# v1-hbridge.net
KiCad netlist of a schematic drawn in EAGLE
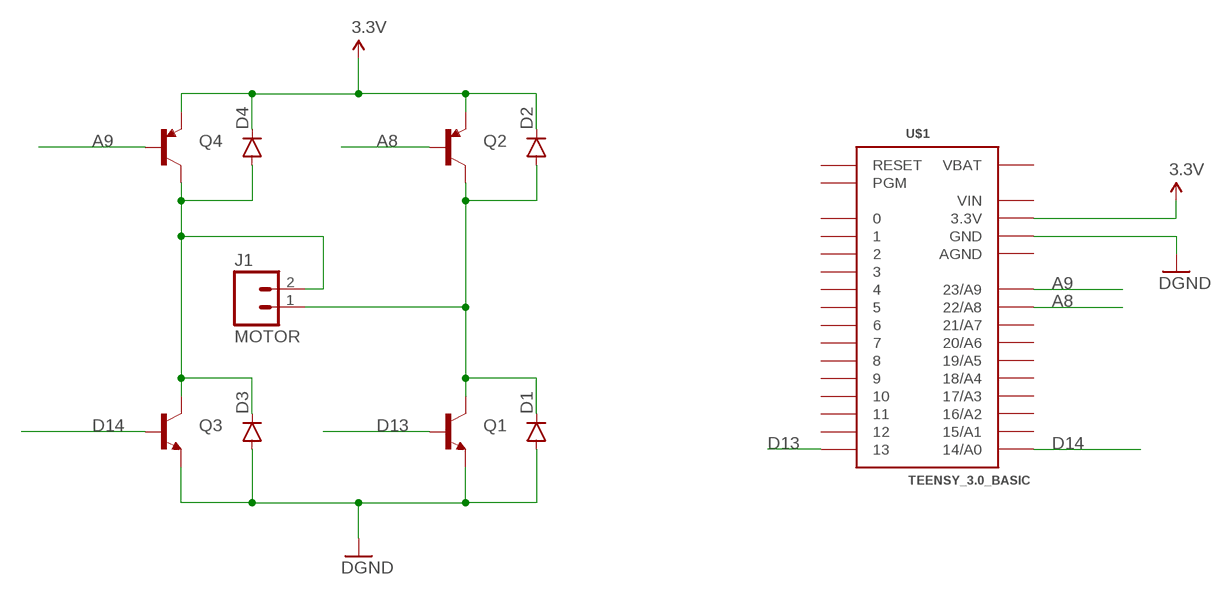
[diagram p0: schematic, sheet 1]

(export (version "E")
  (design (tool "Eeschema 10.0.6"))
  (components
    (comp (ref "D1")
      (value "DIODE")
      (footprint "eagle-import:DIODE-1N4001-KIT")
      (libsource (lib "eagle-import") (part "DIODE"))
    )
    (comp (ref "D2")
      (value "DIODE")
      (footprint "eagle-import:DIODE-1N4001-KIT")
      (libsource (lib "eagle-import") (part "DIODE"))
    )
    (comp (ref "D3")
      (value "DIODE")
      (footprint "eagle-import:DIODE-1N4001-KIT")
      (libsource (lib "eagle-import") (part "DIODE"))
    )
    (comp (ref "D4")
      (value "DIODE")
      (footprint "eagle-import:DIODE-1N4001-KIT")
      (libsource (lib "eagle-import") (part "DIODE"))
    )
    (comp (ref "J1")
      (value "MOTOR")
      (footprint "eagle-import:1X02_LOCK")
      (libsource (lib "eagle-import") (part "M02LOCK"))
    )
    (comp (ref "Q1")
      (value "TRANSISTOR_NPNBC547")
      (footprint "eagle-import:TO-92-AMMO")
      (libsource (lib "eagle-import") (part "TRANSISTOR_NPNBC547"))
    )
    (comp (ref "Q2")
      (value "TRANSISTOR_PNPTO92")
      (footprint "eagle-import:TO-92")
      (libsource (lib "eagle-import") (part "TRANSISTOR_PNPTO92"))
    )
    (comp (ref "Q3")
      (value "TRANSISTOR_NPNBC547")
      (footprint "eagle-import:TO-92-AMMO")
      (libsource (lib "eagle-import") (part "TRANSISTOR_NPNBC547"))
    )
    (comp (ref "Q4")
      (value "TRANSISTOR_PNPTO92")
      (footprint "eagle-import:TO-92")
      (libsource (lib "eagle-import") (part "TRANSISTOR_PNPTO92"))
    )
    (comp (ref "U$1")
      (value "TEENSY_3.0_BASIC")
      (footprint "eagle-import:TEENSY_3.0_BASIC")
      (libsource (lib "eagle-import") (part "TEENSY_3.0_BASIC"))
    )
  )
  (nets
    (net (code "1") (name "/A8") (class "Default")
      (node (ref "Q2") (pin "2") (pinfunction "B_2") (pintype "passive"))
      (node (ref "U$1") (pin "22/A8") (pinfunction "22/A8_22/A8") (pintype "bidirectional"))
    )
    (net (code "2") (name "/A9") (class "Default")
      (node (ref "Q4") (pin "2") (pinfunction "B_2") (pintype "passive"))
      (node (ref "U$1") (pin "23/A9") (pinfunction "23/A9_23/A9") (pintype "bidirectional"))
    )
    (net (code "3") (name "/AGND") (class "Default")
      (node (ref "U$1") (pin "AGND") (pinfunction "AGND_AGND") (pintype "power_in"))
    )
    (net (code "4") (name "/D13") (class "Default")
      (node (ref "Q1") (pin "2") (pinfunction "B_2") (pintype "passive"))
      (node (ref "U$1") (pin "13") (pinfunction "13_13") (pintype "bidirectional"))
    )
    (net (code "5") (name "/D14") (class "Default")
      (node (ref "Q3") (pin "2") (pinfunction "B_2") (pintype "passive"))
      (node (ref "U$1") (pin "14/A0") (pinfunction "14/A0_14/A0") (pintype "bidirectional"))
    )
    (net (code "6") (name "/VBAT") (class "Default")
      (node (ref "U$1") (pin "VBAT") (pinfunction "VBAT_VBAT") (pintype "power_in"))
    )
    (net (code "7") (name "/VIN") (class "Default")
      (node (ref "U$1") (pin "VIN") (pinfunction "VIN_VIN") (pintype "power_in"))
    )
    (net (code "8") (name "3.3V") (class "Default")
      (node (ref "D2") (pin "C") (pinfunction "C_C") (pintype "passive"))
      (node (ref "D4") (pin "C") (pinfunction "C_C") (pintype "passive"))
      (node (ref "Q2") (pin "1") (pinfunction "E_1") (pintype "passive"))
      (node (ref "Q4") (pin "1") (pinfunction "E_1") (pintype "passive"))
      (node (ref "U$1") (pin "3.3V") (pinfunction "3.3V_3.3V") (pintype "power_in"))
      (node (ref "U$1") (pin "3.3V1") (pinfunction "3.3V_3.3V1") (pintype "power_in"))
    )
    (net (code "9") (name "DGND") (class "Default")
      (node (ref "D1") (pin "A") (pinfunction "A_A") (pintype "passive"))
      (node (ref "D3") (pin "A") (pinfunction "A_A") (pintype "passive"))
      (node (ref "Q1") (pin "3") (pinfunction "E_3") (pintype "passive"))
      (node (ref "Q3") (pin "3") (pinfunction "E_3") (pintype "passive"))
      (node (ref "U$1") (pin "GND") (pinfunction "GND_GND") (pintype "power_in"))
      (node (ref "U$1") (pin "GND1") (pinfunction "GND_GND1") (pintype "power_in"))
    )
    (net (code "10") (name "Net-(Q1-C)") (class "Default")
      (node (ref "D1") (pin "C") (pinfunction "C_C") (pintype "passive"))
      (node (ref "D2") (pin "A") (pinfunction "A_A") (pintype "passive"))
      (node (ref "J1") (pin "1") (pinfunction "1_1") (pintype "passive"))
      (node (ref "Q1") (pin "1") (pinfunction "C_1") (pintype "passive"))
      (node (ref "Q2") (pin "3") (pinfunction "C_3") (pintype "passive"))
    )
    (net (code "11") (name "Net-(Q3-C)") (class "Default")
      (node (ref "D3") (pin "C") (pinfunction "C_C") (pintype "passive"))
      (node (ref "D4") (pin "A") (pinfunction "A_A") (pintype "passive"))
      (node (ref "J1") (pin "2") (pinfunction "2_2") (pintype "passive"))
      (node (ref "Q3") (pin "1") (pinfunction "C_1") (pintype "passive"))
      (node (ref "Q4") (pin "3") (pinfunction "C_3") (pintype "passive"))
    )
    (net (code "12") (name "unconnected-(U$1-Pad0)") (class "Default")
      (node (ref "U$1") (pin "0") (pinfunction "0_0") (pintype "bidirectional"))
    )
    (net (code "13") (name "unconnected-(U$1-Pad1)") (class "Default")
      (node (ref "U$1") (pin "1") (pinfunction "1_1") (pintype "bidirectional"))
    )
    (net (code "14") (name "unconnected-(U$1-Pad2)") (class "Default")
      (node (ref "U$1") (pin "2") (pinfunction "2_2") (pintype "bidirectional"))
    )
    (net (code "15") (name "unconnected-(U$1-Pad3)") (class "Default")
      (node (ref "U$1") (pin "3") (pinfunction "3_3") (pintype "bidirectional"))
    )
    (net (code "16") (name "unconnected-(U$1-Pad4)") (class "Default")
      (node (ref "U$1") (pin "4") (pinfunction "4_4") (pintype "bidirectional"))
    )
    (net (code "17") (name "unconnected-(U$1-Pad5)") (class "Default")
      (node (ref "U$1") (pin "5") (pinfunction "5_5") (pintype "bidirectional"))
    )
    (net (code "18") (name "unconnected-(U$1-Pad6)") (class "Default")
      (node (ref "U$1") (pin "6") (pinfunction "6_6") (pintype "bidirectional"))
    )
    (net (code "19") (name "unconnected-(U$1-Pad7)") (class "Default")
      (node (ref "U$1") (pin "7") (pinfunction "7_7") (pintype "bidirectional"))
    )
    (net (code "20") (name "unconnected-(U$1-Pad8)") (class "Default")
      (node (ref "U$1") (pin "8") (pinfunction "8_8") (pintype "bidirectional"))
    )
    (net (code "21") (name "unconnected-(U$1-Pad9)") (class "Default")
      (node (ref "U$1") (pin "9") (pinfunction "9_9") (pintype "bidirectional"))
    )
    (net (code "22") (name "unconnected-(U$1-Pad10)") (class "Default")
      (node (ref "U$1") (pin "10") (pinfunction "10_10") (pintype "bidirectional"))
    )
    (net (code "23") (name "unconnected-(U$1-Pad11)") (class "Default")
      (node (ref "U$1") (pin "11") (pinfunction "11_11") (pintype "bidirectional"))
    )
    (net (code "24") (name "unconnected-(U$1-Pad12)") (class "Default")
      (node (ref "U$1") (pin "12") (pinfunction "12_12") (pintype "bidirectional"))
    )
    (net (code "25") (name "unconnected-(U$1-Pad15{slash}A1)") (class "Default")
      (node (ref "U$1") (pin "15/A1") (pinfunction "15/A1_15/A1") (pintype "bidirectional"))
    )
    (net (code "26") (name "unconnected-(U$1-Pad16{slash}A2)") (class "Default")
      (node (ref "U$1") (pin "16/A2") (pinfunction "16/A2_16/A2") (pintype "bidirectional"))
    )
    (net (code "27") (name "unconnected-(U$1-Pad17{slash}A3)") (class "Default")
      (node (ref "U$1") (pin "17/A3") (pinfunction "17/A3_17/A3") (pintype "bidirectional"))
    )
    (net (code "28") (name "unconnected-(U$1-Pad18{slash}A4)") (class "Default")
      (node (ref "U$1") (pin "18/A4") (pinfunction "18/A4_18/A4") (pintype "bidirectional"))
    )
    (net (code "29") (name "unconnected-(U$1-Pad19{slash}A5)") (class "Default")
      (node (ref "U$1") (pin "19/A5") (pinfunction "19/A5_19/A5") (pintype "bidirectional"))
    )
    (net (code "30") (name "unconnected-(U$1-Pad20{slash}A6)") (class "Default")
      (node (ref "U$1") (pin "20/A6") (pinfunction "20/A6_20/A6") (pintype "bidirectional"))
    )
    (net (code "31") (name "unconnected-(U$1-Pad21{slash}A7)") (class "Default")
      (node (ref "U$1") (pin "21/A7") (pinfunction "21/A7_21/A7") (pintype "bidirectional"))
    )
    (net (code "32") (name "unconnected-(U$1-PadPGM)") (class "Default")
      (node (ref "U$1") (pin "PGM") (pinfunction "PGM_PGM") (pintype "bidirectional"))
    )
    (net (code "33") (name "unconnected-(U$1-PadRESET)") (class "Default")
      (node (ref "U$1") (pin "RESET") (pinfunction "RESET_RESET") (pintype "bidirectional"))
    )
  )
)
